# ADC.net
KiCad netlist of a schematic drawn in Altium Designer
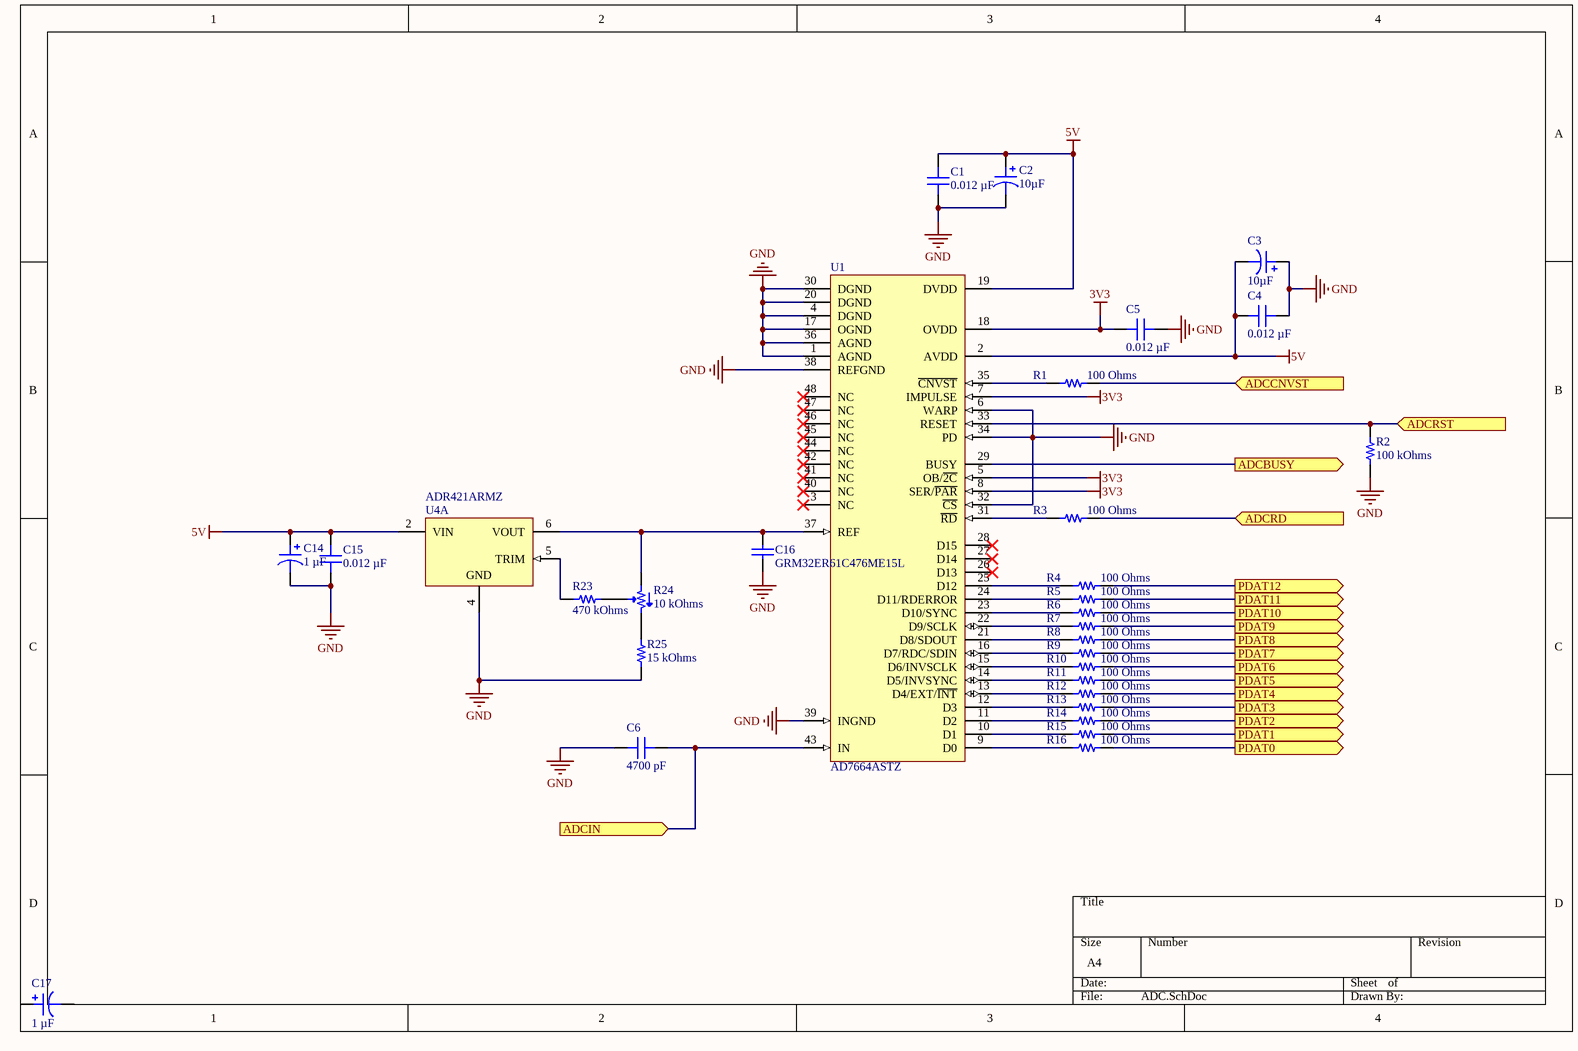
[diagram p0: ADC.SchDoc]

(export (version "E")
  (design (tool "Eeschema 10.0.6"))
  (components
    (comp (ref "C1")
      (value "0.012 µF")
      (footprint "CAP 0603_1608")
      (description "CAP CER 0.012UF 16V X7R 0603")
      (fields (field (name "PART NUMBER") "CC0603KRX7R7BB123") (field (name "MANUFACTURER") "Yageo"))
      (libsource (lib "CAL") (part "Capacitor"))
    )
    (comp (ref "C2")
      (value "10µF")
      (footprint "CAP ALSMD POLY 4.3MM H5.5MM")
      (description "CAP ALUM 10UF 20% 16V SMD")
      (fields (field (name "PART NUMBER") "UWX1C100MCL1GB") (field (name "MANUFACTURER") "Nichicon"))
      (libsource (lib "CAL") (part "Polarised Capacitor"))
    )
    (comp (ref "C3")
      (value "10µF")
      (footprint "CAP ALSMD POLY 4.3MM H5.5MM")
      (description "CAP ALUM 10UF 20% 16V SMD")
      (fields (field (name "PART NUMBER") "UWX1C100MCL1GB") (field (name "MANUFACTURER") "Nichicon"))
      (libsource (lib "") (part "Polarised Capacitor_1"))
    )
    (comp (ref "C4")
      (value "0.012 µF")
      (footprint "CAP 0603_1608")
      (description "CAP CER 0.012UF 16V X7R 0603")
      (fields (field (name "PART NUMBER") "CC0603KRX7R7BB123") (field (name "MANUFACTURER") "Yageo"))
      (libsource (lib "CAL") (part "Capacitor"))
    )
    (comp (ref "C5")
      (value "0.012 µF")
      (footprint "CAP 0603_1608")
      (description "CAP CER 0.012UF 16V X7R 0603")
      (fields (field (name "PART NUMBER") "CC0603KRX7R7BB123") (field (name "MANUFACTURER") "Yageo"))
      (libsource (lib "CAL") (part "Capacitor"))
    )
    (comp (ref "C6")
      (value "4700 pF")
      (footprint "CAP 0603_1608")
      (description "CAP CER 4700PF 16V X7R 0603")
      (fields (field (name "PART NUMBER") "CC0603KRX7R7BB472") (field (name "MANUFACTURER") "Yageo"))
      (libsource (lib "CAL") (part "Capacitor"))
    )
    (comp (ref "C14")
      (value "1 µF")
      (footprint "CAP ALSMD 4.3MM H5.4MM")
      (description "CAP ALUM 1UF 20% 35V SMD")
      (fields
        (field (name "PART NUMBER") "EEE-FC1V1R0R")
        (field (name "MANUFACTURER") "Panasonic Electronic Components")
      )
      (libsource (lib "CAL") (part "Polarised Capacitor"))
    )
    (comp (ref "C15")
      (value "0.012 µF")
      (footprint "CAP 0603_1608")
      (description "CAP CER 0.012UF 16V X7R 0603")
      (fields (field (name "PART NUMBER") "CC0603KRX7R7BB123") (field (name "MANUFACTURER") "Yageo"))
      (libsource (lib "CAL") (part "Capacitor"))
    )
    (comp (ref "C16")
      (value "GRM32ER61C476ME15L")
      (footprint "MURA-1210_H_2.7_M")
      (description "CAP, Ceramic, 47 uF, 20%, 16 V, 1210, RoHS, Tape and Reel")
      (fields (field (name "MANUFACTURER") "Murata") (field (name "TOLERANCE") "20%"))
      (libsource (lib "Altium Content Vault") (part "CAP-NP-2"))
    )
    (comp (ref "C17")
      (value "1 µF")
      (footprint "CAP ALSMD 4.3MM H5.4MM")
      (description "CAP ALUM 1UF 20% 35V SMD")
      (fields
        (field (name "PART NUMBER") "EEE-FC1V1R0R")
        (field (name "MANUFACTURER") "Panasonic Electronic Components")
      )
      (libsource (lib "") (part "Polarised Capacitor_1"))
    )
    (comp (ref "R1")
      (value "100 Ohms")
      (footprint "RES 0603_1608")
      (description "RES 100 OHM 5% 1/10W 0603")
      (fields
        (field (name "PART NUMBER") "WR06X101 JTL")
        (field (name "MANUFACTURER") "Walsin Technology Corporation")
      )
      (libsource (lib "CAL") (part "Resistor"))
    )
    (comp (ref "R2")
      (value "100 kOhms")
      (footprint "RES 0603_1608")
      (description "RES 100K OHM 0.1% 1/16W 0603")
      (fields
        (field (name "PART NUMBER") "RNCS0603BKE100K")
        (field (name "MANUFACTURER") "Stackpole Electronics Inc")
      )
      (libsource (lib "CAL") (part "Resistor"))
    )
    (comp (ref "R3")
      (value "100 Ohms")
      (footprint "RES 0603_1608")
      (description "RES 100 OHM 5% 1/10W 0603")
      (fields
        (field (name "PART NUMBER") "WR06X101 JTL")
        (field (name "MANUFACTURER") "Walsin Technology Corporation")
      )
      (libsource (lib "CAL") (part "Resistor"))
    )
    (comp (ref "R4")
      (value "100 Ohms")
      (footprint "RES 0603_1608")
      (description "RES 100 OHM 5% 1/10W 0603")
      (fields
        (field (name "PART NUMBER") "WR06X101 JTL")
        (field (name "MANUFACTURER") "Walsin Technology Corporation")
      )
      (libsource (lib "CAL") (part "Resistor"))
    )
    (comp (ref "R5")
      (value "100 Ohms")
      (footprint "RES 0603_1608")
      (description "RES 100 OHM 5% 1/10W 0603")
      (fields
        (field (name "PART NUMBER") "WR06X101 JTL")
        (field (name "MANUFACTURER") "Walsin Technology Corporation")
      )
      (libsource (lib "CAL") (part "Resistor"))
    )
    (comp (ref "R6")
      (value "100 Ohms")
      (footprint "RES 0603_1608")
      (description "RES 100 OHM 5% 1/10W 0603")
      (fields
        (field (name "PART NUMBER") "WR06X101 JTL")
        (field (name "MANUFACTURER") "Walsin Technology Corporation")
      )
      (libsource (lib "CAL") (part "Resistor"))
    )
    (comp (ref "R7")
      (value "100 Ohms")
      (footprint "RES 0603_1608")
      (description "RES 100 OHM 5% 1/10W 0603")
      (fields
        (field (name "PART NUMBER") "WR06X101 JTL")
        (field (name "MANUFACTURER") "Walsin Technology Corporation")
      )
      (libsource (lib "CAL") (part "Resistor"))
    )
    (comp (ref "R8")
      (value "100 Ohms")
      (footprint "RES 0603_1608")
      (description "RES 100 OHM 5% 1/10W 0603")
      (fields
        (field (name "PART NUMBER") "WR06X101 JTL")
        (field (name "MANUFACTURER") "Walsin Technology Corporation")
      )
      (libsource (lib "CAL") (part "Resistor"))
    )
    (comp (ref "R9")
      (value "100 Ohms")
      (footprint "RES 0603_1608")
      (description "RES 100 OHM 5% 1/10W 0603")
      (fields
        (field (name "PART NUMBER") "WR06X101 JTL")
        (field (name "MANUFACTURER") "Walsin Technology Corporation")
      )
      (libsource (lib "CAL") (part "Resistor"))
    )
    (comp (ref "R10")
      (value "100 Ohms")
      (footprint "RES 0603_1608")
      (description "RES 100 OHM 5% 1/10W 0603")
      (fields
        (field (name "PART NUMBER") "WR06X101 JTL")
        (field (name "MANUFACTURER") "Walsin Technology Corporation")
      )
      (libsource (lib "CAL") (part "Resistor"))
    )
    (comp (ref "R11")
      (value "100 Ohms")
      (footprint "RES 0603_1608")
      (description "RES 100 OHM 5% 1/10W 0603")
      (fields
        (field (name "PART NUMBER") "WR06X101 JTL")
        (field (name "MANUFACTURER") "Walsin Technology Corporation")
      )
      (libsource (lib "CAL") (part "Resistor"))
    )
    (comp (ref "R12")
      (value "100 Ohms")
      (footprint "RES 0603_1608")
      (description "RES 100 OHM 5% 1/10W 0603")
      (fields
        (field (name "PART NUMBER") "WR06X101 JTL")
        (field (name "MANUFACTURER") "Walsin Technology Corporation")
      )
      (libsource (lib "CAL") (part "Resistor"))
    )
    (comp (ref "R13")
      (value "100 Ohms")
      (footprint "RES 0603_1608")
      (description "RES 100 OHM 5% 1/10W 0603")
      (fields
        (field (name "PART NUMBER") "WR06X101 JTL")
        (field (name "MANUFACTURER") "Walsin Technology Corporation")
      )
      (libsource (lib "CAL") (part "Resistor"))
    )
    (comp (ref "R14")
      (value "100 Ohms")
      (footprint "RES 0603_1608")
      (description "RES 100 OHM 5% 1/10W 0603")
      (fields
        (field (name "PART NUMBER") "WR06X101 JTL")
        (field (name "MANUFACTURER") "Walsin Technology Corporation")
      )
      (libsource (lib "CAL") (part "Resistor"))
    )
    (comp (ref "R15")
      (value "100 Ohms")
      (footprint "RES 0603_1608")
      (description "RES 100 OHM 5% 1/10W 0603")
      (fields
        (field (name "PART NUMBER") "WR06X101 JTL")
        (field (name "MANUFACTURER") "Walsin Technology Corporation")
      )
      (libsource (lib "CAL") (part "Resistor"))
    )
    (comp (ref "R16")
      (value "100 Ohms")
      (footprint "RES 0603_1608")
      (description "RES 100 OHM 5% 1/10W 0603")
      (fields
        (field (name "PART NUMBER") "WR06X101 JTL")
        (field (name "MANUFACTURER") "Walsin Technology Corporation")
      )
      (libsource (lib "CAL") (part "Resistor"))
    )
    (comp (ref "R23")
      (value "470 kOhms")
      (footprint "RES 0603_1608")
      (description "RES 470K OHM 0.1% 1/5W 0603")
      (fields
        (field (name "PART NUMBER") "RS73G1JTTD4703B")
        (field (name "MANUFACTURER") "KOA Speer Electronics, Inc.")
      )
      (libsource (lib "CAL") (part "Resistor"))
    )
    (comp (ref "R24")
      (value "10 kOhms")
      (footprint "POT BOURNS TRIMPOT TC33")
      (description "TRIMMER 10K OHM 0.1W J LEAD TOP")
      (fields (field (name "PART NUMBER") "TC33X-2-103E") (field (name "MANUFACTURER") "Bourns Inc."))
      (libsource (lib "CAL") (part "Potentiometer"))
    )
    (comp (ref "R25")
      (value "15 kOhms")
      (footprint "RES 0603_1608")
      (description "RES 15K OHM 0.05% 1/8W 0603")
      (fields
        (field (name "PART NUMBER") "ERA-3VRW1502V")
        (field (name "MANUFACTURER") "Panasonic Electronic Components")
      )
      (libsource (lib "CAL") (part "Resistor"))
    )
    (comp (ref "U1")
      (value "AD7664ASTZ")
      (footprint "ST-48_N")
      (fields (field (name "GENERIC PART NUMBER") "AD7664") (field (name "MANUFACTURER") "Analog Devices"))
      (libsource (lib "Altium Content Vault") (part "ADI-AD7664-ST-48"))
    )
    (comp (ref "U4")
      (value "ADR421ARMZ")
      (footprint "ADI-RM-8_N")
      (fields (field (name "MANUFACTURER") "Analog Devices"))
      (libsource (lib "Altium Content Vault") (part "ADI-ADR4XX-8"))
    )
  )
  (nets
    (net (code "1") (name "/ADCBUSY") (class "Default")
      (node (ref "U1") (pin "29") (pinfunction "BUSY_29") (pintype "tri_state"))
    )
    (net (code "2") (name "/ADCCNVST") (class "Default")
      (node (ref "R1") (pin "2") (pinfunction "2_2") (pintype "passive"))
    )
    (net (code "3") (name "/ADCIN") (class "Default")
      (node (ref "C6") (pin "2") (pinfunction "2_2") (pintype "passive"))
      (node (ref "U1") (pin "43") (pinfunction "IN_43") (pintype "input"))
    )
    (net (code "4") (name "/ADCRD") (class "Default")
      (node (ref "R3") (pin "2") (pinfunction "2_2") (pintype "passive"))
    )
    (net (code "5") (name "/ADCRST") (class "Default")
      (node (ref "R2") (pin "2") (pinfunction "2_2") (pintype "passive"))
      (node (ref "U1") (pin "33") (pinfunction "RESET_33") (pintype "input"))
    )
    (net (code "6") (name "/PDAT0") (class "Default")
      (node (ref "R16") (pin "2") (pinfunction "2_2") (pintype "passive"))
    )
    (net (code "7") (name "/PDAT1") (class "Default")
      (node (ref "R15") (pin "2") (pinfunction "2_2") (pintype "passive"))
    )
    (net (code "8") (name "/PDAT2") (class "Default")
      (node (ref "R14") (pin "2") (pinfunction "2_2") (pintype "passive"))
    )
    (net (code "9") (name "/PDAT3") (class "Default")
      (node (ref "R13") (pin "2") (pinfunction "2_2") (pintype "passive"))
    )
    (net (code "10") (name "/PDAT4") (class "Default")
      (node (ref "R12") (pin "2") (pinfunction "2_2") (pintype "passive"))
    )
    (net (code "11") (name "/PDAT5") (class "Default")
      (node (ref "R11") (pin "2") (pinfunction "2_2") (pintype "passive"))
    )
    (net (code "12") (name "/PDAT6") (class "Default")
      (node (ref "R10") (pin "2") (pinfunction "2_2") (pintype "passive"))
    )
    (net (code "13") (name "/PDAT7") (class "Default")
      (node (ref "R9") (pin "2") (pinfunction "2_2") (pintype "passive"))
    )
    (net (code "14") (name "/PDAT8") (class "Default")
      (node (ref "R8") (pin "2") (pinfunction "2_2") (pintype "passive"))
    )
    (net (code "15") (name "/PDAT9") (class "Default")
      (node (ref "R7") (pin "2") (pinfunction "2_2") (pintype "passive"))
    )
    (net (code "16") (name "/PDAT10") (class "Default")
      (node (ref "R6") (pin "2") (pinfunction "2_2") (pintype "passive"))
    )
    (net (code "17") (name "/PDAT11") (class "Default")
      (node (ref "R5") (pin "2") (pinfunction "2_2") (pintype "passive"))
    )
    (net (code "18") (name "/PDAT12") (class "Default")
      (node (ref "R4") (pin "2") (pinfunction "2_2") (pintype "passive"))
    )
    (net (code "19") (name "3V3") (class "Default")
      (node (ref "C5") (pin "2") (pinfunction "2_2") (pintype "passive"))
      (node (ref "U1") (pin "18") (pinfunction "OVDD_18") (pintype "power_in"))
      (node (ref "U1") (pin "5") (pinfunction "OB/~{2C}_5") (pintype "input"))
      (node (ref "U1") (pin "7") (pinfunction "IMPULSE_7") (pintype "input"))
      (node (ref "U1") (pin "8") (pinfunction "SER/~{PAR}_8") (pintype "input"))
    )
    (net (code "20") (name "5V") (class "Default")
      (node (ref "C1") (pin "2") (pinfunction "2_2") (pintype "passive"))
      (node (ref "C14") (pin "1") (pinfunction "1_1") (pintype "passive"))
      (node (ref "C15") (pin "2") (pinfunction "2_2") (pintype "passive"))
      (node (ref "C2") (pin "1") (pinfunction "1_1") (pintype "passive"))
      (node (ref "C3") (pin "2") (pinfunction "2_2") (pintype "passive"))
      (node (ref "C4") (pin "2") (pinfunction "2_2") (pintype "passive"))
      (node (ref "U1") (pin "19") (pinfunction "DVDD_19") (pintype "power_in"))
      (node (ref "U1") (pin "2") (pinfunction "AVDD_2") (pintype "power_in"))
      (node (ref "U4") (pin "2") (pinfunction "VIN_2") (pintype "power_in"))
    )
    (net (code "21") (name "GND") (class "Default")
      (node (ref "C1") (pin "1") (pinfunction "1_1") (pintype "passive"))
      (node (ref "C14") (pin "2") (pinfunction "2_2") (pintype "passive"))
      (node (ref "C15") (pin "1") (pinfunction "1_1") (pintype "passive"))
      (node (ref "C16") (pin "1") (pinfunction "1_1") (pintype "passive"))
      (node (ref "C2") (pin "2") (pinfunction "2_2") (pintype "passive"))
      (node (ref "C3") (pin "1") (pinfunction "1_1") (pintype "passive"))
      (node (ref "C4") (pin "1") (pinfunction "1_1") (pintype "passive"))
      (node (ref "C5") (pin "1") (pinfunction "1_1") (pintype "passive"))
      (node (ref "C6") (pin "1") (pinfunction "1_1") (pintype "passive"))
      (node (ref "R2") (pin "1") (pinfunction "1_1") (pintype "passive"))
      (node (ref "R25") (pin "1") (pinfunction "1_1") (pintype "passive"))
      (node (ref "U1") (pin "1") (pinfunction "AGND_1") (pintype "power_in"))
      (node (ref "U1") (pin "17") (pinfunction "OGND_17") (pintype "power_in"))
      (node (ref "U1") (pin "20") (pinfunction "DGND_20") (pintype "power_in"))
      (node (ref "U1") (pin "30") (pinfunction "DGND_30") (pintype "power_in"))
      (node (ref "U1") (pin "32") (pinfunction "~{CS}_32") (pintype "input"))
      (node (ref "U1") (pin "34") (pinfunction "PD_34") (pintype "input"))
      (node (ref "U1") (pin "36") (pinfunction "AGND_36") (pintype "power_in"))
      (node (ref "U1") (pin "38") (pinfunction "REFGND_38") (pintype "power_in"))
      (node (ref "U1") (pin "39") (pinfunction "INGND_39") (pintype "input"))
      (node (ref "U1") (pin "4") (pinfunction "DGND_4") (pintype "power_in"))
      (node (ref "U1") (pin "6") (pinfunction "WARP_6") (pintype "input"))
      (node (ref "U4") (pin "4") (pinfunction "GND_4") (pintype "power_in"))
    )
    (net (code "22") (name "Net-(R23-Pad2)") (class "Default")
      (node (ref "R23") (pin "2") (pinfunction "2_2") (pintype "passive"))
      (node (ref "R24") (pin "2") (pinfunction "2_2") (pintype "passive"))
    )
    (net (code "23") (name "Net-(R24-Pad3)") (class "Default")
      (node (ref "R24") (pin "3") (pinfunction "3_3") (pintype "passive"))
      (node (ref "R25") (pin "2") (pinfunction "2_2") (pintype "passive"))
    )
    (net (code "24") (name "Net-(U1-D0)") (class "Default")
      (node (ref "R16") (pin "1") (pinfunction "1_1") (pintype "passive"))
      (node (ref "U1") (pin "9") (pinfunction "D0_9") (pintype "tri_state"))
    )
    (net (code "25") (name "Net-(U1-D1)") (class "Default")
      (node (ref "R15") (pin "1") (pinfunction "1_1") (pintype "passive"))
      (node (ref "U1") (pin "10") (pinfunction "D1_10") (pintype "tri_state"))
    )
    (net (code "26") (name "Net-(U1-D2)") (class "Default")
      (node (ref "R14") (pin "1") (pinfunction "1_1") (pintype "passive"))
      (node (ref "U1") (pin "11") (pinfunction "D2_11") (pintype "tri_state"))
    )
    (net (code "27") (name "Net-(U1-D3)") (class "Default")
      (node (ref "R13") (pin "1") (pinfunction "1_1") (pintype "passive"))
      (node (ref "U1") (pin "12") (pinfunction "D3_12") (pintype "tri_state"))
    )
    (net (code "28") (name "Net-(U1-D4{slash}EXT{slash}~{INT})") (class "Default")
      (node (ref "R12") (pin "1") (pinfunction "1_1") (pintype "passive"))
      (node (ref "U1") (pin "13") (pinfunction "D4/EXT/~{INT}_13") (pintype "bidirectional"))
    )
    (net (code "29") (name "Net-(U1-D5{slash}INVSYNC)") (class "Default")
      (node (ref "R11") (pin "1") (pinfunction "1_1") (pintype "passive"))
      (node (ref "U1") (pin "14") (pinfunction "D5/INVSYNC_14") (pintype "bidirectional"))
    )
    (net (code "30") (name "Net-(U1-D6{slash}INVSCLK)") (class "Default")
      (node (ref "R10") (pin "1") (pinfunction "1_1") (pintype "passive"))
      (node (ref "U1") (pin "15") (pinfunction "D6/INVSCLK_15") (pintype "bidirectional"))
    )
    (net (code "31") (name "Net-(U1-D7{slash}RDC{slash}SDIN)") (class "Default")
      (node (ref "R9") (pin "1") (pinfunction "1_1") (pintype "passive"))
      (node (ref "U1") (pin "16") (pinfunction "D7/RDC/SDIN_16") (pintype "bidirectional"))
    )
    (net (code "32") (name "Net-(U1-D8{slash}SDOUT)") (class "Default")
      (node (ref "R8") (pin "1") (pinfunction "1_1") (pintype "passive"))
      (node (ref "U1") (pin "21") (pinfunction "D8/SDOUT_21") (pintype "tri_state"))
    )
    (net (code "33") (name "Net-(U1-D9{slash}SCLK)") (class "Default")
      (node (ref "R7") (pin "1") (pinfunction "1_1") (pintype "passive"))
      (node (ref "U1") (pin "22") (pinfunction "D9/SCLK_22") (pintype "bidirectional"))
    )
    (net (code "34") (name "Net-(U1-D10{slash}SYNC)") (class "Default")
      (node (ref "R6") (pin "1") (pinfunction "1_1") (pintype "passive"))
      (node (ref "U1") (pin "23") (pinfunction "D10/SYNC_23") (pintype "tri_state"))
    )
    (net (code "35") (name "Net-(U1-D11{slash}RDERROR)") (class "Default")
      (node (ref "R5") (pin "1") (pinfunction "1_1") (pintype "passive"))
      (node (ref "U1") (pin "24") (pinfunction "D11/RDERROR_24") (pintype "tri_state"))
    )
    (net (code "36") (name "Net-(U1-D12)") (class "Default")
      (node (ref "R4") (pin "1") (pinfunction "1_1") (pintype "passive"))
      (node (ref "U1") (pin "25") (pinfunction "D12_25") (pintype "tri_state"))
    )
    (net (code "37") (name "Net-(U1-REF)") (class "Default")
      (node (ref "C16") (pin "2") (pinfunction "2_2") (pintype "passive"))
      (node (ref "R24") (pin "1") (pinfunction "1_1") (pintype "passive"))
      (node (ref "U1") (pin "37") (pinfunction "REF_37") (pintype "input"))
      (node (ref "U4") (pin "6") (pinfunction "VOUT_6") (pintype "power_in"))
    )
    (net (code "38") (name "Net-(U1-~{CNVST})") (class "Default")
      (node (ref "R1") (pin "1") (pinfunction "1_1") (pintype "passive"))
      (node (ref "U1") (pin "35") (pinfunction "~{CNVST}_35") (pintype "input"))
    )
    (net (code "39") (name "Net-(U1-~{RD})") (class "Default")
      (node (ref "R3") (pin "1") (pinfunction "1_1") (pintype "passive"))
      (node (ref "U1") (pin "31") (pinfunction "~{RD}_31") (pintype "input"))
    )
    (net (code "40") (name "Net-(U4A-TRIM)") (class "Default")
      (node (ref "R23") (pin "1") (pinfunction "1_1") (pintype "passive"))
      (node (ref "U4") (pin "5") (pinfunction "TRIM_5") (pintype "input"))
    )
    (net (code "41") (name "unconnected-(C17-Pad1)") (class "Default")
      (node (ref "C17") (pin "1") (pinfunction "1_1") (pintype "passive"))
    )
    (net (code "42") (name "unconnected-(C17-Pad2)") (class "Default")
      (node (ref "C17") (pin "2") (pinfunction "2_2") (pintype "passive"))
    )
    (net (code "43") (name "unconnected-(U1-D13-Pad26)") (class "Default")
      (node (ref "U1") (pin "26") (pinfunction "D13_26") (pintype "tri_state+no_connect"))
    )
    (net (code "44") (name "unconnected-(U1-D14-Pad27)") (class "Default")
      (node (ref "U1") (pin "27") (pinfunction "D14_27") (pintype "tri_state+no_connect"))
    )
    (net (code "45") (name "unconnected-(U1-D15-Pad28)") (class "Default")
      (node (ref "U1") (pin "28") (pinfunction "D15_28") (pintype "tri_state+no_connect"))
    )
    (net (code "46") (name "unconnected-(U1-NC-Pad3)") (class "Default")
      (node (ref "U1") (pin "3") (pinfunction "NC_3") (pintype "passive+no_connect"))
    )
    (net (code "47") (name "unconnected-(U1-NC-Pad40)") (class "Default")
      (node (ref "U1") (pin "40") (pinfunction "NC_40") (pintype "passive+no_connect"))
    )
    (net (code "48") (name "unconnected-(U1-NC-Pad41)") (class "Default")
      (node (ref "U1") (pin "41") (pinfunction "NC_41") (pintype "passive+no_connect"))
    )
    (net (code "49") (name "unconnected-(U1-NC-Pad42)") (class "Default")
      (node (ref "U1") (pin "42") (pinfunction "NC_42") (pintype "passive+no_connect"))
    )
    (net (code "50") (name "unconnected-(U1-NC-Pad44)") (class "Default")
      (node (ref "U1") (pin "44") (pinfunction "NC_44") (pintype "passive+no_connect"))
    )
    (net (code "51") (name "unconnected-(U1-NC-Pad45)") (class "Default")
      (node (ref "U1") (pin "45") (pinfunction "NC_45") (pintype "passive+no_connect"))
    )
    (net (code "52") (name "unconnected-(U1-NC-Pad46)") (class "Default")
      (node (ref "U1") (pin "46") (pinfunction "NC_46") (pintype "passive+no_connect"))
    )
    (net (code "53") (name "unconnected-(U1-NC-Pad47)") (class "Default")
      (node (ref "U1") (pin "47") (pinfunction "NC_47") (pintype "passive+no_connect"))
    )
    (net (code "54") (name "unconnected-(U1-NC-Pad48)") (class "Default")
      (node (ref "U1") (pin "48") (pinfunction "NC_48") (pintype "passive+no_connect"))
    )
  )
)
